# Shruthi-Analog-SVF-v03.net
KiCad netlist of a schematic drawn in EAGLE
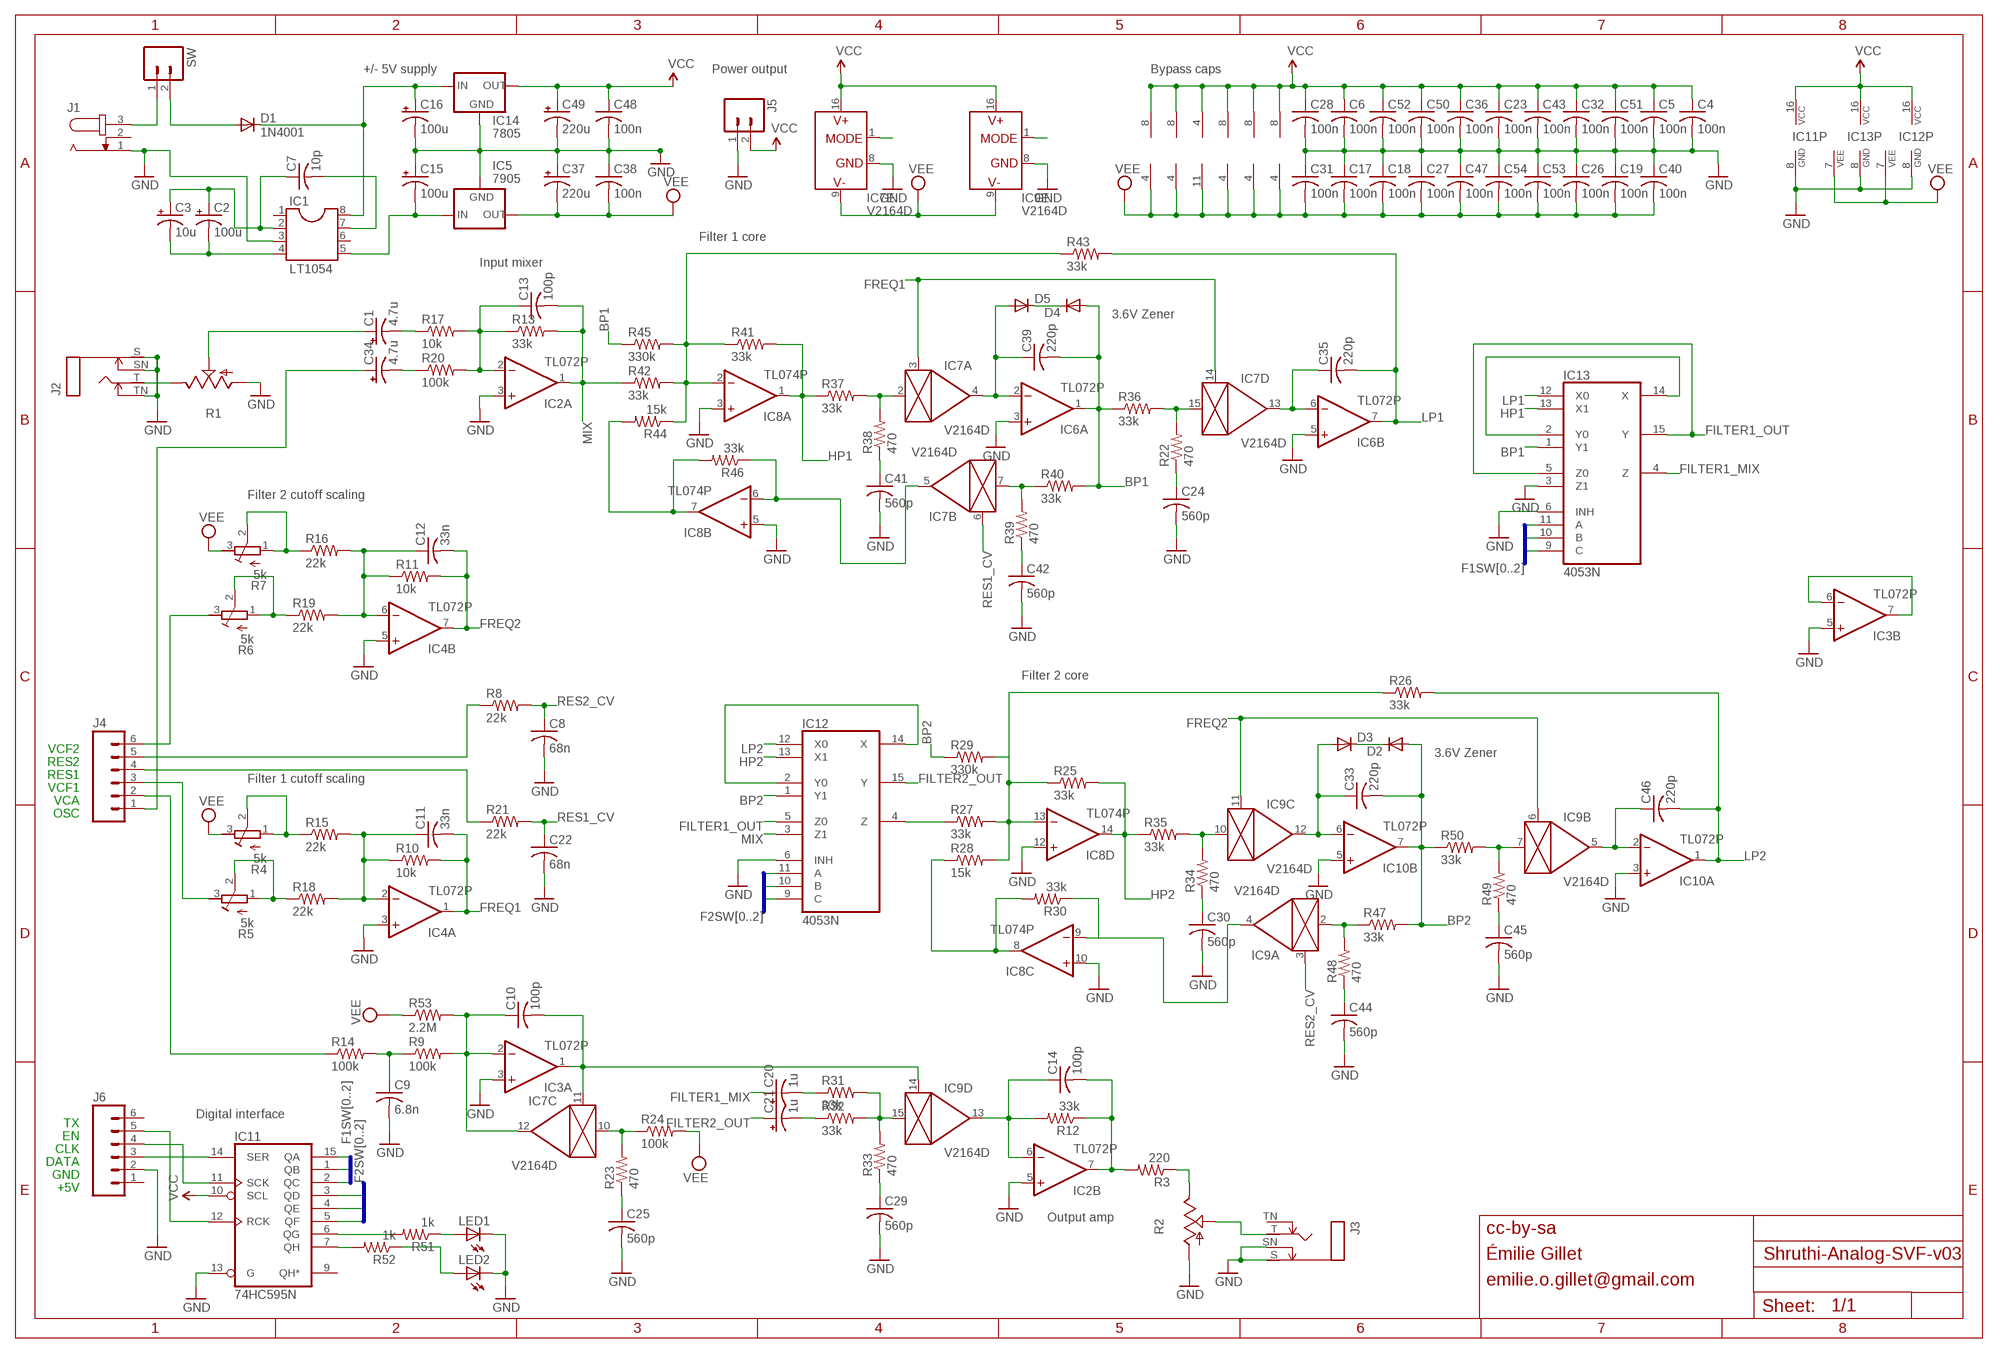
[diagram p0: schematic, sheet 1]

(export (version "E")
  (design (tool "Eeschema 10.0.6"))
  (components
    (comp (ref "C1")
      (value "4.7u")
      (footprint "eagle-import:E2,5-6")
      (libsource (lib "eagle-import") (part "CPOL-USE2.5-6"))
    )
    (comp (ref "C2")
      (value "100u")
      (footprint "eagle-import:E2,5-6")
      (libsource (lib "eagle-import") (part "CPOL-USE2.5-6"))
    )
    (comp (ref "C3")
      (value "10u")
      (footprint "eagle-import:E2,5-5")
      (libsource (lib "eagle-import") (part "CPOL-USE2.5-5"))
    )
    (comp (ref "C4")
      (value "100n")
      (footprint "eagle-import:C025-025X050")
      (libsource (lib "eagle-import") (part "C-US025-025X050"))
    )
    (comp (ref "C5")
      (value "100n")
      (footprint "eagle-import:C025-025X050")
      (libsource (lib "eagle-import") (part "C-US025-025X050"))
    )
    (comp (ref "C6")
      (value "100n")
      (footprint "eagle-import:C025-025X050")
      (libsource (lib "eagle-import") (part "C-US025-025X050"))
    )
    (comp (ref "C7")
      (value "10p")
      (footprint "eagle-import:C025-025X050")
      (libsource (lib "eagle-import") (part "C-US025-025X050"))
    )
    (comp (ref "C8")
      (value "68n")
      (footprint "eagle-import:C050-025X075")
      (libsource (lib "eagle-import") (part "C-US050-025X075"))
    )
    (comp (ref "C9")
      (value "6.8n")
      (footprint "eagle-import:C025-025X050")
      (libsource (lib "eagle-import") (part "C-US025-025X050"))
    )
    (comp (ref "C10")
      (value "100p")
      (footprint "eagle-import:C025-025X050")
      (libsource (lib "eagle-import") (part "C-US025-025X050"))
    )
    (comp (ref "C11")
      (value "33n")
      (footprint "eagle-import:C050-025X075")
      (libsource (lib "eagle-import") (part "C-US050-025X075"))
    )
    (comp (ref "C12")
      (value "33n")
      (footprint "eagle-import:C050-025X075")
      (libsource (lib "eagle-import") (part "C-US050-025X075"))
    )
    (comp (ref "C13")
      (value "100p")
      (footprint "eagle-import:C025-025X050")
      (libsource (lib "eagle-import") (part "C-US025-025X050"))
    )
    (comp (ref "C14")
      (value "100p")
      (footprint "eagle-import:C025-025X050")
      (libsource (lib "eagle-import") (part "C-US025-025X050"))
    )
    (comp (ref "C15")
      (value "100u")
      (footprint "eagle-import:E2,5-7")
      (libsource (lib "eagle-import") (part "CPOL-USE2.5-7"))
    )
    (comp (ref "C16")
      (value "100u")
      (footprint "eagle-import:E2,5-7")
      (libsource (lib "eagle-import") (part "CPOL-USE2.5-7"))
    )
    (comp (ref "C17")
      (value "100n")
      (footprint "eagle-import:C025-025X050")
      (libsource (lib "eagle-import") (part "C-US025-025X050"))
    )
    (comp (ref "C18")
      (value "100n")
      (footprint "eagle-import:C025-025X050")
      (libsource (lib "eagle-import") (part "C-US025-025X050"))
    )
    (comp (ref "C19")
      (value "100n")
      (footprint "eagle-import:C025-025X050")
      (libsource (lib "eagle-import") (part "C-US025-025X050"))
    )
    (comp (ref "C20")
      (value "1u")
      (footprint "eagle-import:E2-5")
      (libsource (lib "eagle-import") (part "CPOL-USE2-5"))
    )
    (comp (ref "C21")
      (value "1u")
      (footprint "eagle-import:E2-5")
      (libsource (lib "eagle-import") (part "CPOL-USE2-5"))
    )
    (comp (ref "C22")
      (value "68n")
      (footprint "eagle-import:C050-025X075")
      (libsource (lib "eagle-import") (part "C-US050-025X075"))
    )
    (comp (ref "C23")
      (value "100n")
      (footprint "eagle-import:C025-025X050")
      (libsource (lib "eagle-import") (part "C-US025-025X050"))
    )
    (comp (ref "C24")
      (value "560p")
      (footprint "eagle-import:C025-025X050")
      (libsource (lib "eagle-import") (part "C-US025-025X050"))
    )
    (comp (ref "C25")
      (value "560p")
      (footprint "eagle-import:C025-025X050")
      (libsource (lib "eagle-import") (part "C-US025-025X050"))
    )
    (comp (ref "C26")
      (value "100n")
      (footprint "eagle-import:C025-025X050")
      (libsource (lib "eagle-import") (part "C-US025-025X050"))
    )
    (comp (ref "C27")
      (value "100n")
      (footprint "eagle-import:C025-025X050")
      (libsource (lib "eagle-import") (part "C-US025-025X050"))
    )
    (comp (ref "C28")
      (value "100n")
      (footprint "eagle-import:C025-025X050")
      (libsource (lib "eagle-import") (part "C-US025-025X050"))
    )
    (comp (ref "C29")
      (value "560p")
      (footprint "eagle-import:C025-025X050")
      (libsource (lib "eagle-import") (part "C-US025-025X050"))
    )
    (comp (ref "C30")
      (value "560p")
      (footprint "eagle-import:C025-025X050")
      (libsource (lib "eagle-import") (part "C-US025-025X050"))
    )
    (comp (ref "C31")
      (value "100n")
      (footprint "eagle-import:C025-025X050")
      (libsource (lib "eagle-import") (part "C-US025-025X050"))
    )
    (comp (ref "C32")
      (value "100n")
      (footprint "eagle-import:C025-025X050")
      (libsource (lib "eagle-import") (part "C-US025-025X050"))
    )
    (comp (ref "C33")
      (value "220p")
      (footprint "eagle-import:C025-025X050")
      (libsource (lib "eagle-import") (part "C-US025-025X050"))
    )
    (comp (ref "C34")
      (value "4.7u")
      (footprint "eagle-import:E2,5-6")
      (libsource (lib "eagle-import") (part "CPOL-USE2.5-6"))
    )
    (comp (ref "C35")
      (value "220p")
      (footprint "eagle-import:C025-025X050")
      (libsource (lib "eagle-import") (part "C-US025-025X050"))
    )
    (comp (ref "C36")
      (value "100n")
      (footprint "eagle-import:C025-025X050")
      (libsource (lib "eagle-import") (part "C-US025-025X050"))
    )
    (comp (ref "C37")
      (value "220u")
      (footprint "eagle-import:E5-10,5")
      (libsource (lib "eagle-import") (part "CPOL-USE5-10.5"))
    )
    (comp (ref "C38")
      (value "100n")
      (footprint "eagle-import:C025-025X050")
      (libsource (lib "eagle-import") (part "C-US025-025X050"))
    )
    (comp (ref "C39")
      (value "220p")
      (footprint "eagle-import:C025-025X050")
      (libsource (lib "eagle-import") (part "C-US025-025X050"))
    )
    (comp (ref "C40")
      (value "100n")
      (footprint "eagle-import:C025-025X050")
      (libsource (lib "eagle-import") (part "C-US025-025X050"))
    )
    (comp (ref "C41")
      (value "560p")
      (footprint "eagle-import:C025-025X050")
      (libsource (lib "eagle-import") (part "C-US025-025X050"))
    )
    (comp (ref "C42")
      (value "560p")
      (footprint "eagle-import:C025-025X050")
      (libsource (lib "eagle-import") (part "C-US025-025X050"))
    )
    (comp (ref "C43")
      (value "100n")
      (footprint "eagle-import:C025-025X050")
      (libsource (lib "eagle-import") (part "C-US025-025X050"))
    )
    (comp (ref "C44")
      (value "560p")
      (footprint "eagle-import:C025-025X050")
      (libsource (lib "eagle-import") (part "C-US025-025X050"))
    )
    (comp (ref "C45")
      (value "560p")
      (footprint "eagle-import:C025-025X050")
      (libsource (lib "eagle-import") (part "C-US025-025X050"))
    )
    (comp (ref "C46")
      (value "220p")
      (footprint "eagle-import:C025-025X050")
      (libsource (lib "eagle-import") (part "C-US025-025X050"))
    )
    (comp (ref "C47")
      (value "100n")
      (footprint "eagle-import:C025-025X050")
      (libsource (lib "eagle-import") (part "C-US025-025X050"))
    )
    (comp (ref "C48")
      (value "100n")
      (footprint "eagle-import:C025-025X050")
      (libsource (lib "eagle-import") (part "C-US025-025X050"))
    )
    (comp (ref "C49")
      (value "220u")
      (footprint "eagle-import:E5-10,5")
      (libsource (lib "eagle-import") (part "CPOL-USE5-10.5"))
    )
    (comp (ref "C50")
      (value "100n")
      (footprint "eagle-import:C025-025X050")
      (libsource (lib "eagle-import") (part "C-US025-025X050"))
    )
    (comp (ref "C51")
      (value "100n")
      (footprint "eagle-import:C025-025X050")
      (libsource (lib "eagle-import") (part "C-US025-025X050"))
    )
    (comp (ref "C52")
      (value "100n")
      (footprint "eagle-import:C025-025X050")
      (libsource (lib "eagle-import") (part "C-US025-025X050"))
    )
    (comp (ref "C53")
      (value "100n")
      (footprint "eagle-import:C025-025X050")
      (libsource (lib "eagle-import") (part "C-US025-025X050"))
    )
    (comp (ref "C54")
      (value "100n")
      (footprint "eagle-import:C025-025X050")
      (libsource (lib "eagle-import") (part "C-US025-025X050"))
    )
    (comp (ref "D1")
      (value "1N4001")
      (footprint "eagle-import:DO41-10")
      (libsource (lib "eagle-import") (part "1N4004"))
    )
    (comp (ref "D2")
      (value "DIODE-D-5")
      (footprint "eagle-import:D-5")
      (libsource (lib "eagle-import") (part "DIODE-D-5"))
    )
    (comp (ref "D3")
      (value "DIODE-D-5")
      (footprint "eagle-import:D-5")
      (libsource (lib "eagle-import") (part "DIODE-D-5"))
    )
    (comp (ref "D4")
      (value "DIODE-D-5")
      (footprint "eagle-import:D-5")
      (libsource (lib "eagle-import") (part "DIODE-D-5"))
    )
    (comp (ref "D5")
      (value "DIODE-D-5")
      (footprint "eagle-import:D-5")
      (libsource (lib "eagle-import") (part "DIODE-D-5"))
    )
    (comp (ref "IC1")
      (value "LT1054")
      (footprint "eagle-import:DIL08")
      (libsource (lib "eagle-import") (part "DIL8"))
    )
    (comp (ref "IC2")
      (value "TL072P")
      (footprint "eagle-import:DIL08")
      (libsource (lib "eagle-import") (part "TL072P"))
    )
    (comp (ref "IC3")
      (value "TL072P")
      (footprint "eagle-import:DIL08")
      (libsource (lib "eagle-import") (part "TL072P"))
    )
    (comp (ref "IC4")
      (value "TL072P")
      (footprint "eagle-import:DIL08")
      (libsource (lib "eagle-import") (part "TL072P"))
    )
    (comp (ref "IC5")
      (value "7905")
      (footprint "eagle-import:79XXS")
      (libsource (lib "eagle-import") (part "79XXS"))
    )
    (comp (ref "IC6")
      (value "TL072P")
      (footprint "eagle-import:DIL08")
      (libsource (lib "eagle-import") (part "TL072P"))
    )
    (comp (ref "IC7")
      (value "V2164D")
      (footprint "eagle-import:DIL16")
      (libsource (lib "eagle-import") (part "SSM2164P"))
    )
    (comp (ref "IC8")
      (value "TL074P")
      (footprint "eagle-import:DIL14")
      (libsource (lib "eagle-import") (part "TL074P"))
    )
    (comp (ref "IC9")
      (value "V2164D")
      (footprint "eagle-import:DIL16")
      (libsource (lib "eagle-import") (part "SSM2164P"))
    )
    (comp (ref "IC10")
      (value "TL072P")
      (footprint "eagle-import:DIL08")
      (libsource (lib "eagle-import") (part "TL072P"))
    )
    (comp (ref "IC11")
      (value "74HC595N")
      (footprint "eagle-import:DIL16")
      (libsource (lib "eagle-import") (part "74595NHC"))
    )
    (comp (ref "IC12")
      (value "4053N")
      (footprint "eagle-import:DIL16")
      (libsource (lib "eagle-import") (part "4053N"))
    )
    (comp (ref "IC13")
      (value "4053N")
      (footprint "eagle-import:DIL16")
      (libsource (lib "eagle-import") (part "4053N"))
    )
    (comp (ref "IC14")
      (value "7805")
      (footprint "eagle-import:78XXS")
      (libsource (lib "eagle-import") (part "78XXS"))
    )
    (comp (ref "J1")
      (value "JACK-PLUG2")
      (footprint "eagle-import:SPC4078_BIG_HOLES")
      (libsource (lib "eagle-import") (part "JACK-PLUG2"))
    )
    (comp (ref "J2")
      (value "MONOSWS")
      (footprint "eagle-import:NMJ4HC-S")
      (libsource (lib "eagle-import") (part "MONOSWS"))
    )
    (comp (ref "J3")
      (value "MONOSWS")
      (footprint "eagle-import:NMJ4HC-S")
      (libsource (lib "eagle-import") (part "MONOSWS"))
    )
    (comp (ref "J4")
      (value "M06SIP")
      (footprint "eagle-import:1X06")
      (libsource (lib "eagle-import") (part "M06SIP"))
    )
    (comp (ref "J5")
      (value "M02PTH")
      (footprint "eagle-import:1X02")
      (libsource (lib "eagle-import") (part "M02PTH"))
    )
    (comp (ref "J6")
      (value "M06SIP")
      (footprint "eagle-import:1X06")
      (libsource (lib "eagle-import") (part "M06SIP"))
    )
    (comp (ref "LED1")
      (value "LEDCHIP-LED0603")
      (footprint "eagle-import:CHIP-LED0603")
      (libsource (lib "eagle-import") (part "LEDCHIP-LED0603"))
    )
    (comp (ref "LED2")
      (value "LEDCHIP-LED0603")
      (footprint "eagle-import:CHIP-LED0603")
      (libsource (lib "eagle-import") (part "LEDCHIP-LED0603"))
    )
    (comp (ref "R1")
      (value "POT_USCABLED")
      (footprint "eagle-import:CABLE_POT_6MM")
      (libsource (lib "eagle-import") (part "POT_USCABLED"))
    )
    (comp (ref "R2")
      (value "POT_USCABLED")
      (footprint "eagle-import:CABLE_POT_6MM")
      (libsource (lib "eagle-import") (part "POT_USCABLED"))
    )
    (comp (ref "R3")
      (value "220")
      (footprint "eagle-import:0204_7")
      (libsource (lib "eagle-import") (part "R-US_0204/7"))
    )
    (comp (ref "R4")
      (value "5k")
      (footprint "eagle-import:RTRIM3296X")
      (libsource (lib "eagle-import") (part "R-TRIMM3296X"))
    )
    (comp (ref "R5")
      (value "5k")
      (footprint "eagle-import:RTRIM3296X")
      (libsource (lib "eagle-import") (part "R-TRIMM3296X"))
    )
    (comp (ref "R6")
      (value "5k")
      (footprint "eagle-import:RTRIM3296X")
      (libsource (lib "eagle-import") (part "R-TRIMM3296X"))
    )
    (comp (ref "R7")
      (value "5k")
      (footprint "eagle-import:RTRIM3296X")
      (libsource (lib "eagle-import") (part "R-TRIMM3296X"))
    )
    (comp (ref "R8")
      (value "22k")
      (footprint "eagle-import:0204_7")
      (libsource (lib "eagle-import") (part "R-US_0204/7"))
    )
    (comp (ref "R9")
      (value "100k")
      (footprint "eagle-import:0204_7")
      (libsource (lib "eagle-import") (part "R-US_0204/7"))
    )
    (comp (ref "R10")
      (value "10k")
      (footprint "eagle-import:0204_7")
      (libsource (lib "eagle-import") (part "R-US_0204/7"))
    )
    (comp (ref "R11")
      (value "10k")
      (footprint "eagle-import:0204_7")
      (libsource (lib "eagle-import") (part "R-US_0204/7"))
    )
    (comp (ref "R12")
      (value "33k")
      (footprint "eagle-import:0204_7")
      (libsource (lib "eagle-import") (part "R-US_0204/7"))
    )
    (comp (ref "R13")
      (value "33k")
      (footprint "eagle-import:0204_7")
      (libsource (lib "eagle-import") (part "R-US_0204/7"))
    )
    (comp (ref "R14")
      (value "100k")
      (footprint "eagle-import:0204_7")
      (libsource (lib "eagle-import") (part "R-US_0204/7"))
    )
    (comp (ref "R15")
      (value "22k")
      (footprint "eagle-import:0204_7")
      (libsource (lib "eagle-import") (part "R-US_0204/7"))
    )
    (comp (ref "R16")
      (value "22k")
      (footprint "eagle-import:0204_7")
      (libsource (lib "eagle-import") (part "R-US_0204/7"))
    )
    (comp (ref "R17")
      (value "10k")
      (footprint "eagle-import:0204_7")
      (libsource (lib "eagle-import") (part "R-US_0204/7"))
    )
    (comp (ref "R18")
      (value "22k")
      (footprint "eagle-import:0204_7")
      (libsource (lib "eagle-import") (part "R-US_0204/7"))
    )
    (comp (ref "R19")
      (value "22k")
      (footprint "eagle-import:0204_7")
      (libsource (lib "eagle-import") (part "R-US_0204/7"))
    )
    (comp (ref "R20")
      (value "100k")
      (footprint "eagle-import:0204_7")
      (libsource (lib "eagle-import") (part "R-US_0204/7"))
    )
    (comp (ref "R21")
      (value "22k")
      (footprint "eagle-import:0204_7")
      (libsource (lib "eagle-import") (part "R-US_0204/7"))
    )
    (comp (ref "R22")
      (value "470")
      (footprint "eagle-import:0204_7")
      (libsource (lib "eagle-import") (part "R-US_0204/7"))
    )
    (comp (ref "R23")
      (value "470")
      (footprint "eagle-import:0204_7")
      (libsource (lib "eagle-import") (part "R-US_0204/7"))
    )
    (comp (ref "R24")
      (value "100k")
      (footprint "eagle-import:0204_7")
      (libsource (lib "eagle-import") (part "R-US_0204/7"))
    )
    (comp (ref "R25")
      (value "33k")
      (footprint "eagle-import:0204_7")
      (libsource (lib "eagle-import") (part "R-US_0204/7"))
    )
    (comp (ref "R26")
      (value "33k")
      (footprint "eagle-import:0204_7")
      (libsource (lib "eagle-import") (part "R-US_0204/7"))
    )
    (comp (ref "R27")
      (value "33k")
      (footprint "eagle-import:0204_7")
      (libsource (lib "eagle-import") (part "R-US_0204/7"))
    )
    (comp (ref "R28")
      (value "15k")
      (footprint "eagle-import:0204_7")
      (libsource (lib "eagle-import") (part "R-US_0204/7"))
    )
    (comp (ref "R29")
      (value "330k")
      (footprint "eagle-import:0204_7")
      (libsource (lib "eagle-import") (part "R-US_0204/7"))
    )
    (comp (ref "R30")
      (value "33k")
      (footprint "eagle-import:0204_7")
      (libsource (lib "eagle-import") (part "R-US_0204/7"))
    )
    (comp (ref "R31")
      (value "33k")
      (footprint "eagle-import:0204_7")
      (libsource (lib "eagle-import") (part "R-US_0204/7"))
    )
    (comp (ref "R32")
      (value "33k")
      (footprint "eagle-import:0204_7")
      (libsource (lib "eagle-import") (part "R-US_0204/7"))
    )
    (comp (ref "R33")
      (value "470")
      (footprint "eagle-import:0204_7")
      (libsource (lib "eagle-import") (part "R-US_0204/7"))
    )
    (comp (ref "R34")
      (value "470")
      (footprint "eagle-import:0204_7")
      (libsource (lib "eagle-import") (part "R-US_0204/7"))
    )
    (comp (ref "R35")
      (value "33k")
      (footprint "eagle-import:0204_7")
      (libsource (lib "eagle-import") (part "R-US_0204/7"))
    )
    (comp (ref "R36")
      (value "33k")
      (footprint "eagle-import:0204_7")
      (libsource (lib "eagle-import") (part "R-US_0204/7"))
    )
    (comp (ref "R37")
      (value "33k")
      (footprint "eagle-import:0204_7")
      (libsource (lib "eagle-import") (part "R-US_0204/7"))
    )
    (comp (ref "R38")
      (value "470")
      (footprint "eagle-import:0204_7")
      (libsource (lib "eagle-import") (part "R-US_0204/7"))
    )
    (comp (ref "R39")
      (value "470")
      (footprint "eagle-import:0204_7")
      (libsource (lib "eagle-import") (part "R-US_0204/7"))
    )
    (comp (ref "R40")
      (value "33k")
      (footprint "eagle-import:0204_7")
      (libsource (lib "eagle-import") (part "R-US_0204/7"))
    )
    (comp (ref "R41")
      (value "33k")
      (footprint "eagle-import:0204_7")
      (libsource (lib "eagle-import") (part "R-US_0204/7"))
    )
    (comp (ref "R42")
      (value "33k")
      (footprint "eagle-import:0204_7")
      (libsource (lib "eagle-import") (part "R-US_0204/7"))
    )
    (comp (ref "R43")
      (value "33k")
      (footprint "eagle-import:0204_7")
      (libsource (lib "eagle-import") (part "R-US_0204/7"))
    )
    (comp (ref "R44")
      (value "15k")
      (footprint "eagle-import:0204_7")
      (libsource (lib "eagle-import") (part "R-US_0204/7"))
    )
    (comp (ref "R45")
      (value "330k")
      (footprint "eagle-import:0204_7")
      (libsource (lib "eagle-import") (part "R-US_0204/7"))
    )
    (comp (ref "R46")
      (value "33k")
      (footprint "eagle-import:0204_7")
      (libsource (lib "eagle-import") (part "R-US_0204/7"))
    )
    (comp (ref "R47")
      (value "33k")
      (footprint "eagle-import:0204_7")
      (libsource (lib "eagle-import") (part "R-US_0204/7"))
    )
    (comp (ref "R48")
      (value "470")
      (footprint "eagle-import:0204_7")
      (libsource (lib "eagle-import") (part "R-US_0204/7"))
    )
    (comp (ref "R49")
      (value "470")
      (footprint "eagle-import:0204_7")
      (libsource (lib "eagle-import") (part "R-US_0204/7"))
    )
    (comp (ref "R50")
      (value "33k")
      (footprint "eagle-import:0204_7")
      (libsource (lib "eagle-import") (part "R-US_0204/7"))
    )
    (comp (ref "R51")
      (value "1k")
      (footprint "eagle-import:0204_7")
      (libsource (lib "eagle-import") (part "R-US_0204/7"))
    )
    (comp (ref "R52")
      (value "1k")
      (footprint "eagle-import:0204_7")
      (libsource (lib "eagle-import") (part "R-US_0204/7"))
    )
    (comp (ref "R53")
      (value "2.2M")
      (footprint "eagle-import:0204V")
      (libsource (lib "eagle-import") (part "R-US_0204/2V"))
    )
    (comp (ref "SW")
      (value "M02PTH")
      (footprint "eagle-import:1X02")
      (libsource (lib "eagle-import") (part "M02PTH"))
    )
  )
  (nets
    (net (code "1") (name "/BP1") (class "Default")
      (node (ref "C39") (pin "2") (pinfunction "2_2") (pintype "passive"))
      (node (ref "D4") (pin "A") (pinfunction "A_A") (pintype "passive"))
      (node (ref "IC13") (pin "1") (pinfunction "Y1_1") (pintype "bidirectional"))
      (node (ref "IC6") (pin "1") (pinfunction "OUT_1") (pintype "output"))
      (node (ref "R36") (pin "1") (pinfunction "1_1") (pintype "passive"))
      (node (ref "R40") (pin "2") (pinfunction "2_2") (pintype "passive"))
      (node (ref "R45") (pin "1") (pinfunction "1_1") (pintype "passive"))
    )
    (net (code "2") (name "/BP2") (class "Default")
      (node (ref "C33") (pin "2") (pinfunction "2_2") (pintype "passive"))
      (node (ref "D2") (pin "A") (pinfunction "A_A") (pintype "passive"))
      (node (ref "IC10") (pin "7") (pinfunction "OUT_7") (pintype "output"))
      (node (ref "IC12") (pin "1") (pinfunction "Y1_1") (pintype "bidirectional"))
      (node (ref "R29") (pin "1") (pinfunction "1_1") (pintype "passive"))
      (node (ref "R47") (pin "2") (pinfunction "2_2") (pintype "passive"))
      (node (ref "R50") (pin "1") (pinfunction "1_1") (pintype "passive"))
    )
    (net (code "3") (name "/F1SW0") (class "Default")
      (node (ref "IC11") (pin "15") (pinfunction "QA_15") (pintype "tri_state"))
      (node (ref "IC13") (pin "9") (pinfunction "C_9") (pintype "input"))
    )
    (net (code "4") (name "/F1SW1") (class "Default")
      (node (ref "IC11") (pin "1") (pinfunction "QB_1") (pintype "tri_state"))
      (node (ref "IC13") (pin "10") (pinfunction "B_10") (pintype "input"))
    )
    (net (code "5") (name "/F1SW2") (class "Default")
      (node (ref "IC11") (pin "2") (pinfunction "QC_2") (pintype "tri_state"))
      (node (ref "IC13") (pin "11") (pinfunction "A_11") (pintype "input"))
    )
    (net (code "7") (name "/F2SW0") (class "Default")
      (node (ref "IC11") (pin "3") (pinfunction "QD_3") (pintype "tri_state"))
      (node (ref "IC12") (pin "9") (pinfunction "C_9") (pintype "input"))
    )
    (net (code "8") (name "/F2SW1") (class "Default")
      (node (ref "IC11") (pin "4") (pinfunction "QE_4") (pintype "tri_state"))
      (node (ref "IC12") (pin "10") (pinfunction "B_10") (pintype "input"))
    )
    (net (code "9") (name "/F2SW2") (class "Default")
      (node (ref "IC11") (pin "5") (pinfunction "QF_5") (pintype "tri_state"))
      (node (ref "IC12") (pin "11") (pinfunction "A_11") (pintype "input"))
    )
    (net (code "11") (name "/FILTER1_MIX") (class "Default")
      (node (ref "C20") (pin "+") (pinfunction "+_+") (pintype "passive"))
      (node (ref "IC13") (pin "4") (pinfunction "Z_4") (pintype "bidirectional"))
    )
    (net (code "12") (name "/FILTER1_OUT") (class "Default")
      (node (ref "IC12") (pin "5") (pinfunction "Z0_5") (pintype "bidirectional"))
      (node (ref "IC13") (pin "15") (pinfunction "Y_15") (pintype "bidirectional"))
      (node (ref "IC13") (pin "5") (pinfunction "Z0_5") (pintype "bidirectional"))
    )
    (net (code "13") (name "/FILTER2_OUT") (class "Default")
      (node (ref "C21") (pin "+") (pinfunction "+_+") (pintype "passive"))
      (node (ref "IC12") (pin "15") (pinfunction "Y_15") (pintype "bidirectional"))
    )
    (net (code "14") (name "/FREQ1") (class "Default")
      (node (ref "C11") (pin "2") (pinfunction "2_2") (pintype "passive"))
      (node (ref "IC4") (pin "1") (pinfunction "OUT_1") (pintype "output"))
      (node (ref "IC7") (pin "14") (pinfunction "CTRL_14") (pintype "input"))
      (node (ref "IC7") (pin "3") (pinfunction "CTRL_3") (pintype "input"))
      (node (ref "R10") (pin "2") (pinfunction "2_2") (pintype "passive"))
    )
    (net (code "15") (name "/FREQ2") (class "Default")
      (node (ref "C12") (pin "2") (pinfunction "2_2") (pintype "passive"))
      (node (ref "IC4") (pin "7") (pinfunction "OUT_7") (pintype "output"))
      (node (ref "IC9") (pin "11") (pinfunction "CTRL_11") (pintype "input"))
      (node (ref "IC9") (pin "6") (pinfunction "CTRL_6") (pintype "input"))
      (node (ref "R11") (pin "2") (pinfunction "2_2") (pintype "passive"))
    )
    (net (code "16") (name "/HP1") (class "Default")
      (node (ref "IC13") (pin "13") (pinfunction "X1_13") (pintype "bidirectional"))
      (node (ref "IC8") (pin "1") (pinfunction "OUT_1") (pintype "output"))
      (node (ref "R37") (pin "1") (pinfunction "1_1") (pintype "passive"))
      (node (ref "R41") (pin "2") (pinfunction "2_2") (pintype "passive"))
    )
    (net (code "17") (name "/HP2") (class "Default")
      (node (ref "IC12") (pin "13") (pinfunction "X1_13") (pintype "bidirectional"))
      (node (ref "IC8") (pin "14") (pinfunction "OUT_14") (pintype "output"))
      (node (ref "R25") (pin "2") (pinfunction "2_2") (pintype "passive"))
      (node (ref "R35") (pin "1") (pinfunction "1_1") (pintype "passive"))
    )
    (net (code "18") (name "/LP1") (class "Default")
      (node (ref "C35") (pin "2") (pinfunction "2_2") (pintype "passive"))
      (node (ref "IC13") (pin "12") (pinfunction "X0_12") (pintype "bidirectional"))
      (node (ref "IC6") (pin "7") (pinfunction "OUT_7") (pintype "output"))
      (node (ref "R43") (pin "2") (pinfunction "2_2") (pintype "passive"))
    )
    (net (code "19") (name "/LP2") (class "Default")
      (node (ref "C46") (pin "2") (pinfunction "2_2") (pintype "passive"))
      (node (ref "IC10") (pin "1") (pinfunction "OUT_1") (pintype "output"))
      (node (ref "IC12") (pin "12") (pinfunction "X0_12") (pintype "bidirectional"))
      (node (ref "R26") (pin "2") (pinfunction "2_2") (pintype "passive"))
    )
    (net (code "20") (name "/MIX") (class "Default")
      (node (ref "C13") (pin "2") (pinfunction "2_2") (pintype "passive"))
      (node (ref "IC12") (pin "3") (pinfunction "Z1_3") (pintype "bidirectional"))
      (node (ref "IC2") (pin "1") (pinfunction "OUT_1") (pintype "output"))
      (node (ref "R13") (pin "2") (pinfunction "2_2") (pintype "passive"))
      (node (ref "R42") (pin "1") (pinfunction "1_1") (pintype "passive"))
    )
    (net (code "21") (name "/RES1_CV") (class "Default")
      (node (ref "C22") (pin "1") (pinfunction "1_1") (pintype "passive"))
      (node (ref "IC7") (pin "6") (pinfunction "CTRL_6") (pintype "input"))
      (node (ref "R21") (pin "2") (pinfunction "2_2") (pintype "passive"))
    )
    (net (code "22") (name "/RES2_CV") (class "Default")
      (node (ref "C8") (pin "1") (pinfunction "1_1") (pintype "passive"))
      (node (ref "IC9") (pin "3") (pinfunction "CTRL_3") (pintype "input"))
      (node (ref "R8") (pin "2") (pinfunction "2_2") (pintype "passive"))
    )
    (net (code "23") (name "GND") (class "Default")
      (node (ref "C15") (pin "+") (pinfunction "+_+") (pintype "passive"))
      (node (ref "C16") (pin "-") (pinfunction "-_-") (pintype "passive"))
      (node (ref "C17") (pin "1") (pinfunction "1_1") (pintype "passive"))
      (node (ref "C18") (pin "1") (pinfunction "1_1") (pintype "passive"))
      (node (ref "C19") (pin "1") (pinfunction "1_1") (pintype "passive"))
      (node (ref "C22") (pin "2") (pinfunction "2_2") (pintype "passive"))
      (node (ref "C23") (pin "2") (pinfunction "2_2") (pintype "passive"))
      (node (ref "C24") (pin "2") (pinfunction "2_2") (pintype "passive"))
      (node (ref "C25") (pin "2") (pinfunction "2_2") (pintype "passive"))
      (node (ref "C26") (pin "1") (pinfunction "1_1") (pintype "passive"))
      (node (ref "C27") (pin "1") (pinfunction "1_1") (pintype "passive"))
      (node (ref "C28") (pin "2") (pinfunction "2_2") (pintype "passive"))
      (node (ref "C29") (pin "2") (pinfunction "2_2") (pintype "passive"))
      (node (ref "C30") (pin "2") (pinfunction "2_2") (pintype "passive"))
      (node (ref "C31") (pin "1") (pinfunction "1_1") (pintype "passive"))
      (node (ref "C32") (pin "2") (pinfunction "2_2") (pintype "passive"))
      (node (ref "C36") (pin "2") (pinfunction "2_2") (pintype "passive"))
      (node (ref "C37") (pin "+") (pinfunction "+_+") (pintype "passive"))
      (node (ref "C38") (pin "1") (pinfunction "1_1") (pintype "passive"))
      (node (ref "C4") (pin "2") (pinfunction "2_2") (pintype "passive"))
      (node (ref "C40") (pin "1") (pinfunction "1_1") (pintype "passive"))
      (node (ref "C41") (pin "2") (pinfunction "2_2") (pintype "passive"))
      (node (ref "C42") (pin "2") (pinfunction "2_2") (pintype "passive"))
      (node (ref "C43") (pin "2") (pinfunction "2_2") (pintype "passive"))
      (node (ref "C44") (pin "2") (pinfunction "2_2") (pintype "passive"))
      (node (ref "C45") (pin "2") (pinfunction "2_2") (pintype "passive"))
      (node (ref "C47") (pin "1") (pinfunction "1_1") (pintype "passive"))
      (node (ref "C48") (pin "2") (pinfunction "2_2") (pintype "passive"))
      (node (ref "C49") (pin "-") (pinfunction "-_-") (pintype "passive"))
      (node (ref "C5") (pin "2") (pinfunction "2_2") (pintype "passive"))
      (node (ref "C50") (pin "2") (pinfunction "2_2") (pintype "passive"))
      (node (ref "C51") (pin "2") (pinfunction "2_2") (pintype "passive"))
      (node (ref "C52") (pin "2") (pinfunction "2_2") (pintype "passive"))
      (node (ref "C53") (pin "1") (pinfunction "1_1") (pintype "passive"))
      (node (ref "C54") (pin "1") (pinfunction "1_1") (pintype "passive"))
      (node (ref "C6") (pin "2") (pinfunction "2_2") (pintype "passive"))
      (node (ref "C8") (pin "2") (pinfunction "2_2") (pintype "passive"))
      (node (ref "C9") (pin "2") (pinfunction "2_2") (pintype "passive"))
      (node (ref "IC1") (pin "3") (pinfunction "3_3") (pintype "passive"))
      (node (ref "IC10") (pin "3") (pinfunction "+IN_3") (pintype "input"))
      (node (ref "IC10") (pin "5") (pinfunction "+IN_5") (pintype "input"))
      (node (ref "IC11") (pin "13") (pinfunction "G_13") (pintype "input"))
      (node (ref "IC11") (pin "8") (pinfunction "GND_8") (pintype "power_in"))
      (node (ref "IC12") (pin "6") (pinfunction "INH_6") (pintype "input"))
      (node (ref "IC12") (pin "8") (pinfunction "GND_8") (pintype "power_in"))
      (node (ref "IC13") (pin "3") (pinfunction "Z1_3") (pintype "bidirectional"))
      (node (ref "IC13") (pin "6") (pinfunction "INH_6") (pintype "input"))
      (node (ref "IC13") (pin "8") (pinfunction "GND_8") (pintype "power_in"))
      (node (ref "IC14") (pin "GND") (pinfunction "GND_GND") (pintype "input"))
      (node (ref "IC2") (pin "3") (pinfunction "+IN_3") (pintype "input"))
      (node (ref "IC2") (pin "5") (pinfunction "+IN_5") (pintype "input"))
      (node (ref "IC3") (pin "3") (pinfunction "+IN_3") (pintype "input"))
      (node (ref "IC3") (pin "5") (pinfunction "+IN_5") (pintype "input"))
      (node (ref "IC4") (pin "3") (pinfunction "+IN_3") (pintype "input"))
      (node (ref "IC4") (pin "5") (pinfunction "+IN_5") (pintype "input"))
      (node (ref "IC5") (pin "GND") (pinfunction "GND_GND") (pintype "input"))
      (node (ref "IC6") (pin "3") (pinfunction "+IN_3") (pintype "input"))
      (node (ref "IC6") (pin "5") (pinfunction "+IN_5") (pintype "input"))
      (node (ref "IC7") (pin "8") (pinfunction "GND_8") (pintype "power_in"))
      (node (ref "IC8") (pin "10") (pinfunction "+IN_10") (pintype "input"))
      (node (ref "IC8") (pin "12") (pinfunction "+IN_12") (pintype "input"))
      (node (ref "IC8") (pin "3") (pinfunction "+IN_3") (pintype "input"))
      (node (ref "IC8") (pin "5") (pinfunction "+IN_5") (pintype "input"))
      (node (ref "IC9") (pin "8") (pinfunction "GND_8") (pintype "power_in"))
      (node (ref "J1") (pin "1") (pinfunction "1_1") (pintype "passive"))
      (node (ref "J2") (pin "S") (pinfunction "S_S") (pintype "passive"))
      (node (ref "J2") (pin "SN") (pinfunction "SN_SN") (pintype "passive"))
      (node (ref "J2") (pin "TN") (pinfunction "TN_TN") (pintype "passive"))
      (node (ref "J3") (pin "S") (pinfunction "S_S") (pintype "passive"))
      (node (ref "J3") (pin "SN") (pinfunction "SN_SN") (pintype "passive"))
      (node (ref "J5") (pin "1") (pinfunction "1_1") (pintype "passive"))
      (node (ref "J6") (pin "2") (pinfunction "2_2") (pintype "passive"))
      (node (ref "LED1") (pin "C") (pinfunction "C_C") (pintype "passive"))
      (node (ref "LED2") (pin "C") (pinfunction "C_C") (pintype "passive"))
      (node (ref "R1") (pin "A") (pinfunction "A_A") (pintype "passive"))
      (node (ref "R2") (pin "A") (pinfunction "A_A") (pintype "passive"))
    )
    (net (code "24") (name "Net-(C1-Pad+)") (class "Default")
      (node (ref "C1") (pin "+") (pinfunction "+_+") (pintype "passive"))
      (node (ref "R1") (pin "S") (pinfunction "S_S") (pintype "passive"))
    )
    (net (code "25") (name "Net-(C1-Pad-)") (class "Default")
      (node (ref "C1") (pin "-") (pinfunction "-_-") (pintype "passive"))
      (node (ref "R17") (pin "1") (pinfunction "1_1") (pintype "passive"))
    )
    (net (code "26") (name "Net-(C2-Pad+)") (class "Default")
      (node (ref "C2") (pin "+") (pinfunction "+_+") (pintype "passive"))
      (node (ref "C3") (pin "+") (pinfunction "+_+") (pintype "passive"))
      (node (ref "C7") (pin "1") (pinfunction "1_1") (pintype "passive"))
      (node (ref "IC1") (pin "2") (pinfunction "2_2") (pintype "passive"))
    )
    (net (code "27") (name "Net-(C2-Pad-)") (class "Default")
      (node (ref "C2") (pin "-") (pinfunction "-_-") (pintype "passive"))
      (node (ref "C3") (pin "-") (pinfunction "-_-") (pintype "passive"))
      (node (ref "IC1") (pin "4") (pinfunction "4_4") (pintype "passive"))
    )
    (net (code "28") (name "Net-(C7-Pad2)") (class "Default")
      (node (ref "C7") (pin "2") (pinfunction "2_2") (pintype "passive"))
      (node (ref "IC1") (pin "7") (pinfunction "7_7") (pintype "passive"))
    )
    (net (code "29") (name "Net-(C9-Pad1)") (class "Default")
      (node (ref "C9") (pin "1") (pinfunction "1_1") (pintype "passive"))
      (node (ref "R14") (pin "2") (pinfunction "2_2") (pintype "passive"))
      (node (ref "R9") (pin "1") (pinfunction "1_1") (pintype "passive"))
    )
    (net (code "30") (name "Net-(C15-Pad-)") (class "Default")
      (node (ref "C15") (pin "-") (pinfunction "-_-") (pintype "passive"))
      (node (ref "IC1") (pin "5") (pinfunction "5_5") (pintype "passive"))
      (node (ref "IC5") (pin "IN") (pinfunction "IN_IN") (pintype "input"))
    )
    (net (code "31") (name "Net-(C16-Pad+)") (class "Default")
      (node (ref "C16") (pin "+") (pinfunction "+_+") (pintype "passive"))
      (node (ref "D1") (pin "C") (pinfunction "C_C") (pintype "passive"))
      (node (ref "IC1") (pin "8") (pinfunction "8_8") (pintype "passive"))
      (node (ref "IC14") (pin "IN") (pinfunction "IN_IN") (pintype "input"))
    )
    (net (code "32") (name "Net-(C20-Pad-)") (class "Default")
      (node (ref "C20") (pin "-") (pinfunction "-_-") (pintype "passive"))
      (node (ref "R31") (pin "1") (pinfunction "1_1") (pintype "passive"))
    )
    (net (code "33") (name "Net-(C21-Pad-)") (class "Default")
      (node (ref "C21") (pin "-") (pinfunction "-_-") (pintype "passive"))
      (node (ref "R32") (pin "1") (pinfunction "1_1") (pintype "passive"))
    )
    (net (code "34") (name "Net-(C24-Pad1)") (class "Default")
      (node (ref "C24") (pin "1") (pinfunction "1_1") (pintype "passive"))
      (node (ref "R22") (pin "1") (pinfunction "1_1") (pintype "passive"))
    )
    (net (code "35") (name "Net-(C25-Pad1)") (class "Default")
      (node (ref "C25") (pin "1") (pinfunction "1_1") (pintype "passive"))
      (node (ref "R23") (pin "1") (pinfunction "1_1") (pintype "passive"))
    )
    (net (code "36") (name "Net-(C29-Pad1)") (class "Default")
      (node (ref "C29") (pin "1") (pinfunction "1_1") (pintype "passive"))
      (node (ref "R33") (pin "1") (pinfunction "1_1") (pintype "passive"))
    )
    (net (code "37") (name "Net-(C30-Pad1)") (class "Default")
      (node (ref "C30") (pin "1") (pinfunction "1_1") (pintype "passive"))
      (node (ref "R34") (pin "1") (pinfunction "1_1") (pintype "passive"))
    )
    (net (code "38") (name "Net-(C34-Pad+)") (class "Default")
      (node (ref "C34") (pin "+") (pinfunction "+_+") (pintype "passive"))
      (node (ref "J4") (pin "1") (pinfunction "1_1") (pintype "passive"))
    )
    (net (code "39") (name "Net-(C34-Pad-)") (class "Default")
      (node (ref "C34") (pin "-") (pinfunction "-_-") (pintype "passive"))
      (node (ref "R20") (pin "1") (pinfunction "1_1") (pintype "passive"))
    )
    (net (code "40") (name "Net-(C41-Pad1)") (class "Default")
      (node (ref "C41") (pin "1") (pinfunction "1_1") (pintype "passive"))
      (node (ref "R38") (pin "1") (pinfunction "1_1") (pintype "passive"))
    )
    (net (code "41") (name "Net-(C42-Pad1)") (class "Default")
      (node (ref "C42") (pin "1") (pinfunction "1_1") (pintype "passive"))
      (node (ref "R39") (pin "1") (pinfunction "1_1") (pintype "passive"))
    )
    (net (code "42") (name "Net-(C44-Pad1)") (class "Default")
      (node (ref "C44") (pin "1") (pinfunction "1_1") (pintype "passive"))
      (node (ref "R48") (pin "1") (pinfunction "1_1") (pintype "passive"))
    )
    (net (code "43") (name "Net-(C45-Pad1)") (class "Default")
      (node (ref "C45") (pin "1") (pinfunction "1_1") (pintype "passive"))
      (node (ref "R49") (pin "1") (pinfunction "1_1") (pintype "passive"))
    )
    (net (code "44") (name "Net-(D1-PadA)") (class "Default")
      (node (ref "D1") (pin "A") (pinfunction "A_A") (pintype "passive"))
      (node (ref "SW") (pin "2") (pinfunction "2_2") (pintype "passive"))
    )
    (net (code "45") (name "Net-(D2-PadC)") (class "Default")
      (node (ref "D2") (pin "C") (pinfunction "C_C") (pintype "passive"))
      (node (ref "D3") (pin "C") (pinfunction "C_C") (pintype "passive"))
    )
    (net (code "46") (name "Net-(D4-PadC)") (class "Default")
      (node (ref "D4") (pin "C") (pinfunction "C_C") (pintype "passive"))
      (node (ref "D5") (pin "C") (pinfunction "C_C") (pintype "passive"))
    )
    (net (code "47") (name "Net-(IC2A--IN)") (class "Default")
      (node (ref "C13") (pin "1") (pinfunction "1_1") (pintype "passive"))
      (node (ref "IC2") (pin "2") (pinfunction "-IN_2") (pintype "input"))
      (node (ref "R13") (pin "1") (pinfunction "1_1") (pintype "passive"))
      (node (ref "R17") (pin "2") (pinfunction "2_2") (pintype "passive"))
      (node (ref "R20") (pin "2") (pinfunction "2_2") (pintype "passive"))
    )
    (net (code "48") (name "Net-(IC2B--IN)") (class "Default")
      (node (ref "C14") (pin "1") (pinfunction "1_1") (pintype "passive"))
      (node (ref "IC2") (pin "6") (pinfunction "-IN_6") (pintype "input"))
      (node (ref "IC9") (pin "13") (pinfunction "OUT_13") (pintype "output"))
      (node (ref "R12") (pin "2") (pinfunction "2_2") (pintype "passive"))
    )
    (net (code "49") (name "Net-(IC2B-OUT)") (class "Default")
      (node (ref "C14") (pin "2") (pinfunction "2_2") (pintype "passive"))
      (node (ref "IC2") (pin "7") (pinfunction "OUT_7") (pintype "output"))
      (node (ref "R12") (pin "1") (pinfunction "1_1") (pintype "passive"))
      (node (ref "R3") (pin "2") (pinfunction "2_2") (pintype "passive"))
    )
    (net (code "50") (name "Net-(IC3A--IN)") (class "Default")
      (node (ref "C10") (pin "1") (pinfunction "1_1") (pintype "passive"))
      (node (ref "IC3") (pin "2") (pinfunction "-IN_2") (pintype "input"))
      (node (ref "IC7") (pin "12") (pinfunction "OUT_12") (pintype "output"))
      (node (ref "R53") (pin "2") (pinfunction "2_2") (pintype "passive"))
      (node (ref "R9") (pin "2") (pinfunction "2_2") (pintype "passive"))
    )
    (net (code "51") (name "Net-(IC3A-OUT)") (class "Default")
      (node (ref "C10") (pin "2") (pinfunction "2_2") (pintype "passive"))
      (node (ref "IC3") (pin "1") (pinfunction "OUT_1") (pintype "output"))
      (node (ref "IC7") (pin "11") (pinfunction "CTRL_11") (pintype "input"))
      (node (ref "IC9") (pin "14") (pinfunction "CTRL_14") (pintype "input"))
    )
    (net (code "52") (name "Net-(IC3B--IN)") (class "Default")
      (node (ref "IC3") (pin "6") (pinfunction "-IN_6") (pintype "input"))
      (node (ref "IC3") (pin "7") (pinfunction "OUT_7") (pintype "output"))
    )
    (net (code "53") (name "Net-(IC4A--IN)") (class "Default")
      (node (ref "C11") (pin "1") (pinfunction "1_1") (pintype "passive"))
      (node (ref "IC4") (pin "2") (pinfunction "-IN_2") (pintype "input"))
      (node (ref "R10") (pin "1") (pinfunction "1_1") (pintype "passive"))
      (node (ref "R15") (pin "2") (pinfunction "2_2") (pintype "passive"))
      (node (ref "R18") (pin "2") (pinfunction "2_2") (pintype "passive"))
    )
    (net (code "54") (name "Net-(IC4B--IN)") (class "Default")
      (node (ref "C12") (pin "1") (pinfunction "1_1") (pintype "passive"))
      (node (ref "IC4") (pin "6") (pinfunction "-IN_6") (pintype "input"))
      (node (ref "R11") (pin "1") (pinfunction "1_1") (pintype "passive"))
      (node (ref "R16") (pin "2") (pinfunction "2_2") (pintype "passive"))
      (node (ref "R19") (pin "2") (pinfunction "2_2") (pintype "passive"))
    )
    (net (code "55") (name "Net-(IC6A--IN)") (class "Default")
      (node (ref "C39") (pin "1") (pinfunction "1_1") (pintype "passive"))
      (node (ref "D5") (pin "A") (pinfunction "A_A") (pintype "passive"))
      (node (ref "IC6") (pin "2") (pinfunction "-IN_2") (pintype "input"))
      (node (ref "IC7") (pin "4") (pinfunction "OUT_4") (pintype "output"))
    )
    (net (code "56") (name "Net-(IC6B--IN)") (class "Default")
      (node (ref "C35") (pin "1") (pinfunction "1_1") (pintype "passive"))
      (node (ref "IC6") (pin "6") (pinfunction "-IN_6") (pintype "input"))
      (node (ref "IC7") (pin "13") (pinfunction "OUT_13") (pintype "output"))
    )
    (net (code "57") (name "Net-(IC7A-IN)") (class "Default")
      (node (ref "IC7") (pin "2") (pinfunction "IN_2") (pintype "input"))
      (node (ref "R37") (pin "2") (pinfunction "2_2") (pintype "passive"))
      (node (ref "R38") (pin "2") (pinfunction "2_2") (pintype "passive"))
    )
    (net (code "58") (name "Net-(IC7B-IN)") (class "Default")
      (node (ref "IC7") (pin "7") (pinfunction "IN_7") (pintype "input"))
      (node (ref "R39") (pin "2") (pinfunction "2_2") (pintype "passive"))
      (node (ref "R40") (pin "1") (pinfunction "1_1") (pintype "passive"))
    )
    (net (code "59") (name "Net-(IC7B-OUT)") (class "Default")
      (node (ref "IC7") (pin "5") (pinfunction "OUT_5") (pintype "output"))
      (node (ref "IC8") (pin "6") (pinfunction "-IN_6") (pintype "input"))
      (node (ref "R46") (pin "1") (pinfunction "1_1") (pintype "passive"))
    )
    (net (code "60") (name "Net-(IC7C-IN)") (class "Default")
      (node (ref "IC7") (pin "10") (pinfunction "IN_10") (pintype "input"))
      (node (ref "R23") (pin "2") (pinfunction "2_2") (pintype "passive"))
      (node (ref "R24") (pin "1") (pinfunction "1_1") (pintype "passive"))
    )
    (net (code "61") (name "Net-(IC7D-IN)") (class "Default")
      (node (ref "IC7") (pin "15") (pinfunction "IN_15") (pintype "input"))
      (node (ref "R22") (pin "2") (pinfunction "2_2") (pintype "passive"))
      (node (ref "R36") (pin "2") (pinfunction "2_2") (pintype "passive"))
    )
    (net (code "62") (name "Net-(IC8A--IN)") (class "Default")
      (node (ref "IC8") (pin "2") (pinfunction "-IN_2") (pintype "input"))
      (node (ref "R41") (pin "1") (pinfunction "1_1") (pintype "passive"))
      (node (ref "R42") (pin "2") (pinfunction "2_2") (pintype "passive"))
      (node (ref "R43") (pin "1") (pinfunction "1_1") (pintype "passive"))
      (node (ref "R44") (pin "1") (pinfunction "1_1") (pintype "passive"))
      (node (ref "R45") (pin "2") (pinfunction "2_2") (pintype "passive"))
    )
    (net (code "63") (name "Net-(IC8B-OUT)") (class "Default")
      (node (ref "IC8") (pin "7") (pinfunction "OUT_7") (pintype "output"))
      (node (ref "R44") (pin "2") (pinfunction "2_2") (pintype "passive"))
      (node (ref "R46") (pin "2") (pinfunction "2_2") (pintype "passive"))
    )
    (net (code "64") (name "Net-(IC8C--IN)") (class "Default")
      (node (ref "IC8") (pin "9") (pinfunction "-IN_9") (pintype "input"))
      (node (ref "IC9") (pin "4") (pinfunction "OUT_4") (pintype "output"))
      (node (ref "R30") (pin "1") (pinfunction "1_1") (pintype "passive"))
    )
    (net (code "65") (name "Net-(IC8C-OUT)") (class "Default")
      (node (ref "IC8") (pin "8") (pinfunction "OUT_8") (pintype "output"))
      (node (ref "R28") (pin "1") (pinfunction "1_1") (pintype "passive"))
      (node (ref "R30") (pin "2") (pinfunction "2_2") (pintype "passive"))
    )
    (net (code "66") (name "Net-(IC8D--IN)") (class "Default")
      (node (ref "IC8") (pin "13") (pinfunction "-IN_13") (pintype "input"))
      (node (ref "R25") (pin "1") (pinfunction "1_1") (pintype "passive"))
      (node (ref "R26") (pin "1") (pinfunction "1_1") (pintype "passive"))
      (node (ref "R27") (pin "2") (pinfunction "2_2") (pintype "passive"))
      (node (ref "R28") (pin "2") (pinfunction "2_2") (pintype "passive"))
      (node (ref "R29") (pin "2") (pinfunction "2_2") (pintype "passive"))
    )
    (net (code "67") (name "Net-(IC9A-IN)") (class "Default")
      (node (ref "IC9") (pin "2") (pinfunction "IN_2") (pintype "input"))
      (node (ref "R47") (pin "1") (pinfunction "1_1") (pintype "passive"))
      (node (ref "R48") (pin "2") (pinfunction "2_2") (pintype "passive"))
    )
    (net (code "68") (name "Net-(IC9B-IN)") (class "Default")
      (node (ref "IC9") (pin "7") (pinfunction "IN_7") (pintype "input"))
      (node (ref "R49") (pin "2") (pinfunction "2_2") (pintype "passive"))
      (node (ref "R50") (pin "2") (pinfunction "2_2") (pintype "passive"))
    )
    (net (code "69") (name "Net-(IC9C-IN)") (class "Default")
      (node (ref "IC9") (pin "10") (pinfunction "IN_10") (pintype "input"))
      (node (ref "R34") (pin "2") (pinfunction "2_2") (pintype "passive"))
      (node (ref "R35") (pin "2") (pinfunction "2_2") (pintype "passive"))
    )
    (net (code "70") (name "Net-(IC9D-IN)") (class "Default")
      (node (ref "IC9") (pin "15") (pinfunction "IN_15") (pintype "input"))
      (node (ref "R31") (pin "2") (pinfunction "2_2") (pintype "passive"))
      (node (ref "R32") (pin "2") (pinfunction "2_2") (pintype "passive"))
      (node (ref "R33") (pin "2") (pinfunction "2_2") (pintype "passive"))
    )
    (net (code "71") (name "Net-(IC10A--IN)") (class "Default")
      (node (ref "C46") (pin "1") (pinfunction "1_1") (pintype "passive"))
      (node (ref "IC10") (pin "2") (pinfunction "-IN_2") (pintype "input"))
      (node (ref "IC9") (pin "5") (pinfunction "OUT_5") (pintype "output"))
    )
    (net (code "72") (name "Net-(IC10B--IN)") (class "Default")
      (node (ref "C33") (pin "1") (pinfunction "1_1") (pintype "passive"))
      (node (ref "D3") (pin "A") (pinfunction "A_A") (pintype "passive"))
      (node (ref "IC10") (pin "6") (pinfunction "-IN_6") (pintype "input"))
      (node (ref "IC9") (pin "12") (pinfunction "OUT_12") (pintype "output"))
    )
    (net (code "73") (name "Net-(IC11A-QG)") (class "Default")
      (node (ref "IC11") (pin "6") (pinfunction "QG_6") (pintype "tri_state"))
      (node (ref "R51") (pin "2") (pinfunction "2_2") (pintype "passive"))
    )
    (net (code "74") (name "Net-(IC11A-QH)") (class "Default")
      (node (ref "IC11") (pin "7") (pinfunction "QH_7") (pintype "tri_state"))
      (node (ref "R52") (pin "2") (pinfunction "2_2") (pintype "passive"))
    )
    (net (code "75") (name "Net-(IC11A-RCK)") (class "Default")
      (node (ref "IC11") (pin "12") (pinfunction "RCK_12") (pintype "input"))
      (node (ref "J6") (pin "5") (pinfunction "5_5") (pintype "passive"))
    )
    (net (code "76") (name "Net-(IC11A-SCK)") (class "Default")
      (node (ref "IC11") (pin "11") (pinfunction "SCK_11") (pintype "input"))
      (node (ref "J6") (pin "4") (pinfunction "4_4") (pintype "passive"))
    )
    (net (code "77") (name "Net-(IC11A-SER)") (class "Default")
      (node (ref "IC11") (pin "14") (pinfunction "SER_14") (pintype "input"))
      (node (ref "J6") (pin "3") (pinfunction "3_3") (pintype "passive"))
    )
    (net (code "78") (name "Net-(IC12A-X)") (class "Default")
      (node (ref "IC12") (pin "14") (pinfunction "X_14") (pintype "bidirectional"))
      (node (ref "IC12") (pin "2") (pinfunction "Y0_2") (pintype "bidirectional"))
    )
    (net (code "79") (name "Net-(IC12A-Z)") (class "Default")
      (node (ref "IC12") (pin "4") (pinfunction "Z_4") (pintype "bidirectional"))
      (node (ref "R27") (pin "1") (pinfunction "1_1") (pintype "passive"))
    )
    (net (code "80") (name "Net-(IC13A-X)") (class "Default")
      (node (ref "IC13") (pin "14") (pinfunction "X_14") (pintype "bidirectional"))
      (node (ref "IC13") (pin "2") (pinfunction "Y0_2") (pintype "bidirectional"))
    )
    (net (code "81") (name "Net-(J1-Pad3)") (class "Default")
      (node (ref "J1") (pin "3") (pinfunction "3_3") (pintype "passive"))
      (node (ref "SW") (pin "1") (pinfunction "1_1") (pintype "passive"))
    )
    (net (code "82") (name "Net-(J2-PadT)") (class "Default")
      (node (ref "J2") (pin "T") (pinfunction "T_T") (pintype "passive"))
      (node (ref "R1") (pin "E") (pinfunction "E_E") (pintype "passive"))
    )
    (net (code "83") (name "Net-(J3-PadT)") (class "Default")
      (node (ref "J3") (pin "T") (pinfunction "T_T") (pintype "passive"))
      (node (ref "R2") (pin "S") (pinfunction "S_S") (pintype "passive"))
    )
    (net (code "84") (name "Net-(J4-Pad2)") (class "Default")
      (node (ref "J4") (pin "2") (pinfunction "2_2") (pintype "passive"))
      (node (ref "R14") (pin "1") (pinfunction "1_1") (pintype "passive"))
    )
    (net (code "85") (name "Net-(J4-Pad4)") (class "Default")
      (node (ref "J4") (pin "4") (pinfunction "4_4") (pintype "passive"))
      (node (ref "R21") (pin "1") (pinfunction "1_1") (pintype "passive"))
    )
    (net (code "86") (name "Net-(J4-Pad5)") (class "Default")
      (node (ref "J4") (pin "5") (pinfunction "5_5") (pintype "passive"))
      (node (ref "R8") (pin "1") (pinfunction "1_1") (pintype "passive"))
    )
    (net (code "87") (name "Net-(LED1-PadA)") (class "Default")
      (node (ref "LED1") (pin "A") (pinfunction "A_A") (pintype "passive"))
      (node (ref "R51") (pin "1") (pinfunction "1_1") (pintype "passive"))
    )
    (net (code "88") (name "Net-(LED2-PadA)") (class "Default")
      (node (ref "LED2") (pin "A") (pinfunction "A_A") (pintype "passive"))
      (node (ref "R52") (pin "1") (pinfunction "1_1") (pintype "passive"))
    )
    (net (code "89") (name "Net-(R2-PadE)") (class "Default")
      (node (ref "R2") (pin "E") (pinfunction "E_E") (pintype "passive"))
      (node (ref "R3") (pin "1") (pinfunction "1_1") (pintype "passive"))
    )
    (net (code "90") (name "Net-(R4-E)") (class "Default")
      (node (ref "R15") (pin "1") (pinfunction "1_1") (pintype "passive"))
      (node (ref "R4") (pin "1") (pinfunction "E_1") (pintype "passive"))
      (node (ref "R4") (pin "2") (pinfunction "S_2") (pintype "passive"))
    )
    (net (code "91") (name "Net-(R5-A)") (class "Default")
      (node (ref "J4") (pin "3") (pinfunction "3_3") (pintype "passive"))
      (node (ref "R5") (pin "3") (pinfunction "A_3") (pintype "passive"))
    )
    (net (code "92") (name "Net-(R5-E)") (class "Default")
      (node (ref "R18") (pin "1") (pinfunction "1_1") (pintype "passive"))
      (node (ref "R5") (pin "1") (pinfunction "E_1") (pintype "passive"))
      (node (ref "R5") (pin "2") (pinfunction "S_2") (pintype "passive"))
    )
    (net (code "93") (name "Net-(R6-A)") (class "Default")
      (node (ref "J4") (pin "6") (pinfunction "6_6") (pintype "passive"))
      (node (ref "R6") (pin "3") (pinfunction "A_3") (pintype "passive"))
    )
    (net (code "94") (name "Net-(R6-E)") (class "Default")
      (node (ref "R19") (pin "1") (pinfunction "1_1") (pintype "passive"))
      (node (ref "R6") (pin "1") (pinfunction "E_1") (pintype "passive"))
      (node (ref "R6") (pin "2") (pinfunction "S_2") (pintype "passive"))
    )
    (net (code "95") (name "Net-(R7-E)") (class "Default")
      (node (ref "R16") (pin "1") (pinfunction "1_1") (pintype "passive"))
      (node (ref "R7") (pin "1") (pinfunction "E_1") (pintype "passive"))
      (node (ref "R7") (pin "2") (pinfunction "S_2") (pintype "passive"))
    )
    (net (code "96") (name "VCC") (class "Default")
      (node (ref "C23") (pin "1") (pinfunction "1_1") (pintype "passive"))
      (node (ref "C28") (pin "1") (pinfunction "1_1") (pintype "passive"))
      (node (ref "C32") (pin "1") (pinfunction "1_1") (pintype "passive"))
      (node (ref "C36") (pin "1") (pinfunction "1_1") (pintype "passive"))
      (node (ref "C4") (pin "1") (pinfunction "1_1") (pintype "passive"))
      (node (ref "C43") (pin "1") (pinfunction "1_1") (pintype "passive"))
      (node (ref "C48") (pin "1") (pinfunction "1_1") (pintype "passive"))
      (node (ref "C49") (pin "+") (pinfunction "+_+") (pintype "passive"))
      (node (ref "C5") (pin "1") (pinfunction "1_1") (pintype "passive"))
      (node (ref "C50") (pin "1") (pinfunction "1_1") (pintype "passive"))
      (node (ref "C51") (pin "1") (pinfunction "1_1") (pintype "passive"))
      (node (ref "C52") (pin "1") (pinfunction "1_1") (pintype "passive"))
      (node (ref "C6") (pin "1") (pinfunction "1_1") (pintype "passive"))
      (node (ref "IC10") (pin "8") (pinfunction "V+_8") (pintype "power_in"))
      (node (ref "IC11") (pin "10") (pinfunction "SCL_10") (pintype "input"))
      (node (ref "IC11") (pin "16") (pinfunction "VCC_16") (pintype "power_in"))
      (node (ref "IC12") (pin "16") (pinfunction "VCC_16") (pintype "power_in"))
      (node (ref "IC13") (pin "16") (pinfunction "VCC_16") (pintype "power_in"))
      (node (ref "IC14") (pin "OUT") (pinfunction "OUT_OUT") (pintype "passive"))
      (node (ref "IC2") (pin "8") (pinfunction "V+_8") (pintype "power_in"))
      (node (ref "IC3") (pin "8") (pinfunction "V+_8") (pintype "power_in"))
      (node (ref "IC4") (pin "8") (pinfunction "V+_8") (pintype "power_in"))
      (node (ref "IC6") (pin "8") (pinfunction "V+_8") (pintype "power_in"))
      (node (ref "IC7") (pin "16") (pinfunction "V+_16") (pintype "power_in"))
      (node (ref "IC8") (pin "4") (pinfunction "V+_4") (pintype "power_in"))
      (node (ref "IC9") (pin "16") (pinfunction "V+_16") (pintype "power_in"))
      (node (ref "J5") (pin "2") (pinfunction "2_2") (pintype "passive"))
    )
    (net (code "97") (name "VEE") (class "Default")
      (node (ref "C17") (pin "2") (pinfunction "2_2") (pintype "passive"))
      (node (ref "C18") (pin "2") (pinfunction "2_2") (pintype "passive"))
      (node (ref "C19") (pin "2") (pinfunction "2_2") (pintype "passive"))
      (node (ref "C26") (pin "2") (pinfunction "2_2") (pintype "passive"))
      (node (ref "C27") (pin "2") (pinfunction "2_2") (pintype "passive"))
      (node (ref "C31") (pin "2") (pinfunction "2_2") (pintype "passive"))
      (node (ref "C37") (pin "-") (pinfunction "-_-") (pintype "passive"))
      (node (ref "C38") (pin "2") (pinfunction "2_2") (pintype "passive"))
      (node (ref "C40") (pin "2") (pinfunction "2_2") (pintype "passive"))
      (node (ref "C47") (pin "2") (pinfunction "2_2") (pintype "passive"))
      (node (ref "C53") (pin "2") (pinfunction "2_2") (pintype "passive"))
      (node (ref "C54") (pin "2") (pinfunction "2_2") (pintype "passive"))
      (node (ref "IC10") (pin "4") (pinfunction "V-_4") (pintype "power_in"))
      (node (ref "IC12") (pin "7") (pinfunction "VEE_7") (pintype "power_in"))
      (node (ref "IC13") (pin "7") (pinfunction "VEE_7") (pintype "power_in"))
      (node (ref "IC2") (pin "4") (pinfunction "V-_4") (pintype "power_in"))
      (node (ref "IC3") (pin "4") (pinfunction "V-_4") (pintype "power_in"))
      (node (ref "IC4") (pin "4") (pinfunction "V-_4") (pintype "power_in"))
      (node (ref "IC5") (pin "OUT") (pinfunction "OUT_OUT") (pintype "passive"))
      (node (ref "IC6") (pin "4") (pinfunction "V-_4") (pintype "power_in"))
      (node (ref "IC7") (pin "9") (pinfunction "V-_9") (pintype "power_in"))
      (node (ref "IC8") (pin "11") (pinfunction "V-_11") (pintype "power_in"))
      (node (ref "IC9") (pin "9") (pinfunction "V-_9") (pintype "power_in"))
      (node (ref "R24") (pin "2") (pinfunction "2_2") (pintype "passive"))
      (node (ref "R4") (pin "3") (pinfunction "A_3") (pintype "passive"))
      (node (ref "R53") (pin "1") (pinfunction "1_1") (pintype "passive"))
      (node (ref "R7") (pin "3") (pinfunction "A_3") (pintype "passive"))
    )
    (net (code "98") (name "unconnected-(IC1-Pad1)") (class "Default")
      (node (ref "IC1") (pin "1") (pinfunction "1_1") (pintype "passive"))
    )
    (net (code "99") (name "unconnected-(IC1-Pad6)") (class "Default")
      (node (ref "IC1") (pin "6") (pinfunction "6_6") (pintype "passive"))
    )
    (net (code "100") (name "unconnected-(IC7E-MODE-Pad1)") (class "Default")
      (node (ref "IC7") (pin "1") (pinfunction "MODE_1") (pintype "input"))
    )
    (net (code "101") (name "unconnected-(IC9E-MODE-Pad1)") (class "Default")
      (node (ref "IC9") (pin "1") (pinfunction "MODE_1") (pintype "input"))
    )
    (net (code "102") (name "unconnected-(IC11A-QH*-Pad9)") (class "Default")
      (node (ref "IC11") (pin "9") (pinfunction "QH*_9") (pintype "tri_state"))
    )
    (net (code "103") (name "unconnected-(J1-Pad2)") (class "Default")
      (node (ref "J1") (pin "2") (pinfunction "2_2") (pintype "passive"))
    )
    (net (code "104") (name "unconnected-(J3-PadTN)") (class "Default")
      (node (ref "J3") (pin "TN") (pinfunction "TN_TN") (pintype "passive"))
    )
    (net (code "105") (name "unconnected-(J6-Pad1)") (class "Default")
      (node (ref "J6") (pin "1") (pinfunction "1_1") (pintype "passive"))
    )
    (net (code "106") (name "unconnected-(J6-Pad6)") (class "Default")
      (node (ref "J6") (pin "6") (pinfunction "6_6") (pintype "passive"))
    )
  )
)
